# 02-MCU.net
KiCad netlist of a schematic drawn in Altium Designer
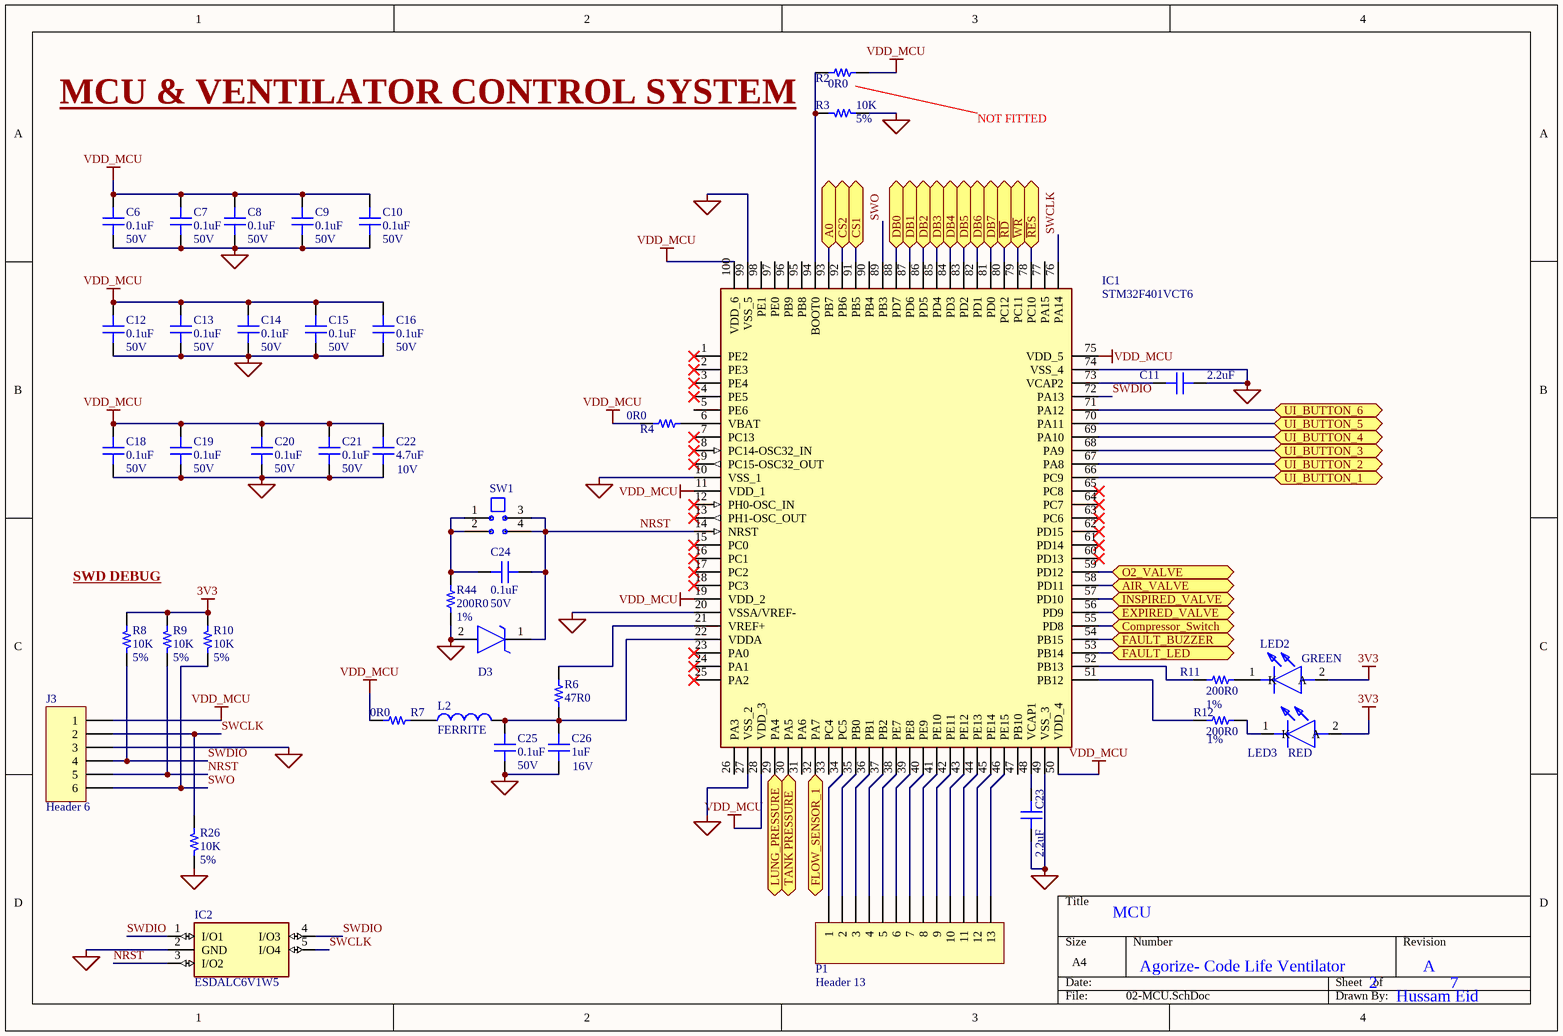
[diagram p0: 02-MCU.SchDoc]

(export (version "E")
  (design (tool "Eeschema 10.0.6"))
  (components
    (comp (ref "C6")
      (value "0.1uF")
      (footprint "CAP 0603/1608")
      (description "CAP CER 0.1UF 50V X7R 0603")
      (fields (field (name "TOLERANCE") "20%") (field (name "VOLTAGE RATING") "50V"))
      (libsource (lib "Celestial Library Database") (part "Capacitor"))
    )
    (comp (ref "C7")
      (value "0.1uF")
      (footprint "CAP 0603/1608")
      (description "CAP CER 0.1UF 50V X7R 0603")
      (fields (field (name "TOLERANCE") "20%") (field (name "VOLTAGE RATING") "50V"))
      (libsource (lib "Celestial Library Database") (part "Capacitor"))
    )
    (comp (ref "C8")
      (value "0.1uF")
      (footprint "CAP 0603/1608")
      (description "CAP CER 0.1UF 50V X7R 0603")
      (fields (field (name "TOLERANCE") "20%") (field (name "VOLTAGE RATING") "50V"))
      (libsource (lib "Celestial Library Database") (part "Capacitor"))
    )
    (comp (ref "C9")
      (value "0.1uF")
      (footprint "CAP 0603/1608")
      (description "CAP CER 0.1UF 50V X7R 0603")
      (fields (field (name "TOLERANCE") "20%") (field (name "VOLTAGE RATING") "50V"))
      (libsource (lib "Celestial Library Database") (part "Capacitor"))
    )
    (comp (ref "C10")
      (value "0.1uF")
      (footprint "CAP 0603/1608")
      (description "CAP CER 0.1UF 50V X7R 0603")
      (fields (field (name "TOLERANCE") "20%") (field (name "VOLTAGE RATING") "50V"))
      (libsource (lib "Celestial Library Database") (part "Capacitor"))
    )
    (comp (ref "C11")
      (value "2.2uF")
      (footprint "CAP 0603/1608")
      (description "CAP CER 2.2UF 16V X5R 0603")
      (fields (field (name "TOLERANCE") "10%") (field (name "VOLTAGE") "16V"))
      (libsource (lib "Celestial Library Database") (part "Capacitor"))
    )
    (comp (ref "C12")
      (value "0.1uF")
      (footprint "CAP 0603/1608")
      (description "CAP CER 0.1UF 50V X7R 0603")
      (fields (field (name "TOLERANCE") "20%") (field (name "VOLTAGE RATING") "50V"))
      (libsource (lib "Celestial Library Database") (part "Capacitor"))
    )
    (comp (ref "C13")
      (value "0.1uF")
      (footprint "CAP 0603/1608")
      (description "CAP CER 0.1UF 50V X7R 0603")
      (fields (field (name "TOLERANCE") "20%") (field (name "VOLTAGE RATING") "50V"))
      (libsource (lib "Celestial Library Database") (part "Capacitor"))
    )
    (comp (ref "C14")
      (value "0.1uF")
      (footprint "CAP 0603/1608")
      (description "CAP CER 0.1UF 50V X7R 0603")
      (fields (field (name "TOLERANCE") "20%") (field (name "VOLTAGE RATING") "50V"))
      (libsource (lib "Celestial Library Database") (part "Capacitor"))
    )
    (comp (ref "C15")
      (value "0.1uF")
      (footprint "CAP 0603/1608")
      (description "CAP CER 0.1UF 50V X7R 0603")
      (fields (field (name "TOLERANCE") "20%") (field (name "VOLTAGE RATING") "50V"))
      (libsource (lib "Celestial Library Database") (part "Capacitor"))
    )
    (comp (ref "C16")
      (value "0.1uF")
      (footprint "CAP 0603/1608")
      (description "CAP CER 0.1UF 50V X7R 0603")
      (fields (field (name "TOLERANCE") "20%") (field (name "VOLTAGE RATING") "50V"))
      (libsource (lib "Celestial Library Database") (part "Capacitor"))
    )
    (comp (ref "C18")
      (value "0.1uF")
      (footprint "CAP 0603/1608")
      (description "CAP CER 0.1UF 50V X7R 0603")
      (fields (field (name "TOLERANCE") "20%") (field (name "VOLTAGE RATING") "50V"))
      (libsource (lib "Celestial Library Database") (part "Capacitor"))
    )
    (comp (ref "C19")
      (value "0.1uF")
      (footprint "CAP 0603/1608")
      (description "CAP CER 0.1UF 50V X7R 0603")
      (fields (field (name "TOLERANCE") "20%") (field (name "VOLTAGE RATING") "50V"))
      (libsource (lib "Celestial Library Database") (part "Capacitor"))
    )
    (comp (ref "C20")
      (value "0.1uF")
      (footprint "CAP 0603/1608")
      (description "CAP CER 0.1UF 50V X7R 0603")
      (fields (field (name "TOLERANCE") "20%") (field (name "VOLTAGE RATING") "50V"))
      (libsource (lib "Celestial Library Database") (part "Capacitor"))
    )
    (comp (ref "C21")
      (value "0.1uF")
      (footprint "CAP 0603/1608")
      (description "CAP CER 0.1UF 50V X7R 0603")
      (fields (field (name "TOLERANCE") "20%") (field (name "VOLTAGE RATING") "50V"))
      (libsource (lib "Celestial Library Database") (part "Capacitor"))
    )
    (comp (ref "C22")
      (value "4.7uF")
      (footprint "CAP 0603/1608")
      (description "CAP CER 4.7UF 10V X5R 0603")
      (fields (field (name "TOLERANCE") "10%") (field (name "VOLTAGE RATING") "10V"))
      (libsource (lib "Celestial Library Database") (part "Capacitor"))
    )
    (comp (ref "C23")
      (value "2.2uF")
      (footprint "CAP 0603/1608")
      (description "CAP CER 2.2UF 16V X5R 0603")
      (fields (field (name "TOLERANCE") "10%") (field (name "VOLTAGE") "16V"))
      (libsource (lib "Celestial Library Database") (part "Capacitor"))
    )
    (comp (ref "C24")
      (value "0.1uF")
      (footprint "CAP 0603/1608")
      (description "CAP CER 0.1UF 50V X7R 0603")
      (fields (field (name "TOLERANCE") "20%") (field (name "VOLTAGE RATING") "50V"))
      (libsource (lib "Celestial Library Database") (part "Capacitor"))
    )
    (comp (ref "C25")
      (value "0.1uF")
      (footprint "CAP 0603/1608")
      (description "CAP CER 0.1UF 50V X7R 0603")
      (fields (field (name "TOLERANCE") "20%") (field (name "VOLTAGE RATING") "50V"))
      (libsource (lib "Celestial Library Database") (part "Capacitor"))
    )
    (comp (ref "C26")
      (value "1uF")
      (footprint "CAP 0603/1608")
      (description "CAP CER 1UF 16V X7R 0603")
      (fields (field (name "TOLERANCE") "20%") (field (name "VOLTAGE RATING (DC)") "16V"))
      (libsource (lib "Celestial Library Database") (part "Capacitor"))
    )
    (comp (ref "D3")
      (value "ESDALC6V1-1U2")
      (footprint "SamacSys:ESDALC6V11U2")
      (description "TVS Diode (Uni-directional)")
      (fields
        (field (name "MOUSER PART NUMBER") "511-ESDALC6V1-1U2")
        (field (name "RS PART NUMBER") "7958404P")
      )
      (libsource (lib "*") (part "ESDALC6V1-1U2"))
    )
    (comp (ref "IC1")
      (value "STM32F401VCT6")
      (footprint "SamacSys:QFP50P1600X1600X160-100N")
      (description "ARM® Cortex®-M4 STM32F4 Microcontroller IC 32-Bit 84MHz 256KB (256K x 8) FLASH 100-LQFP (14x14)")
      (fields
        (field (name "MOUSER PART NUMBER") "511-STM32F401VCT6")
        (field (name "RS PART NUMBER") "7926019P")
      )
      (libsource (lib "*") (part "STM32F401VCT6"))
    )
    (comp (ref "IC2")
      (value "ESDALC6V1W5")
      (footprint "SamacSys:SOT65P210X110-5N")
      (description "Clamp  Ipp Tvs Diode Surface Mount SOT-323-5")
      (fields (field (name "MOUSER PART NUMBER") "511-ESDALC6V1W5") (field (name "RS PART NUMBER") "1787373"))
      (libsource (lib "*") (part "ESDALC6V1W5"))
    )
    (comp (ref "J3")
      (value "Header 6")
      (footprint "HDR1X6")
      (description "Header, 6-Pin")
      (fields (field (name "PUBLISHER") "Altium Limited"))
      (libsource (lib "Miscellaneous Connectors") (part "Header 6"))
    )
    (comp (ref "L2")
      (value "FERRITE")
      (footprint "BEADC1608X95N")
      (description "FERRITE BEAD 300 OHM 0603 1LN")
      (fields (field (name "TOLERANCE") "25%"))
      (libsource (lib "Miscellaneous Devices") (part "Inductor"))
    )
    (comp (ref "LED2")
      (value "GREEN")
      (footprint "SamacSys:150060GS73220")
      (description "LED GREEN CLEAR 0603 SMD")
      (libsource (lib "*") (part "150060GS73220"))
    )
    (comp (ref "LED3")
      (value "RED")
      (footprint "SamacSys:150060GS73220")
      (description "LED GREEN CLEAR 0603 SMD")
      (libsource (lib "*") (part "150060GS73220"))
    )
    (comp (ref "P1")
      (value "Header 13")
      (footprint "HDR1X13")
      (description "Header, 13-Pin")
      (fields (field (name "PUBLISHER") "Altium Limited"))
      (libsource (lib "Miscellaneous Connectors") (part "Header 13"))
    )
    (comp (ref "R2")
      (value "0R0")
      (footprint "RES 0603/1608")
      (description "RES SMD 0 OHM JUMPER 1/10W 0603")
      (fields (field (name "TOLERANCE") "0%"))
      (libsource (lib "Celestial Library Database") (part "Resistor"))
    )
    (comp (ref "R3")
      (value "10K")
      (footprint "RES 0603/1608")
      (description "RES SMD 10K OHM 5% 1/10W 0603")
      (fields (field (name "TOLERANCE") "5%"))
      (libsource (lib "Celestial Library Database") (part "Resistor"))
    )
    (comp (ref "R4")
      (value "0R0")
      (footprint "RES 0603/1608")
      (description "RES SMD 0 OHM JUMPER 1/10W 0603")
      (fields (field (name "TOLERANCE") "0%"))
      (libsource (lib "Celestial Library Database") (part "Resistor"))
    )
    (comp (ref "R6")
      (value "47R0")
      (footprint "RES 0603/1608")
      (description "RESISTOR 47 Ohms ±5% 0.1W, 1/10W Chip Resistor 0603")
      (libsource (lib "Celestial Library Database") (part "Resistor"))
    )
    (comp (ref "R7")
      (value "0R0")
      (footprint "RES 0603/1608")
      (description "RES SMD 0 OHM JUMPER 1/10W 0603")
      (fields (field (name "TOLERANCE") "0%"))
      (libsource (lib "Celestial Library Database") (part "Resistor"))
    )
    (comp (ref "R8")
      (value "10K")
      (footprint "RES 0603/1608")
      (description "RES SMD 10K OHM 5% 1/10W 0603")
      (fields (field (name "TOLERANCE") "5%"))
      (libsource (lib "Celestial Library Database") (part "Resistor"))
    )
    (comp (ref "R9")
      (value "10K")
      (footprint "RES 0603/1608")
      (description "RES SMD 10K OHM 5% 1/10W 0603")
      (fields (field (name "TOLERANCE") "5%"))
      (libsource (lib "Celestial Library Database") (part "Resistor"))
    )
    (comp (ref "R10")
      (value "10K")
      (footprint "RES 0603/1608")
      (description "RES SMD 10K OHM 5% 1/10W 0603")
      (fields (field (name "TOLERANCE") "5%"))
      (libsource (lib "Celestial Library Database") (part "Resistor"))
    )
    (comp (ref "R11")
      (value "200R0")
      (footprint "RES 1206/3216")
      (description "RES SMD 10K OHM 1% 1/4W 1206")
      (fields (field (name "TOLERANCE") "1%"))
      (libsource (lib "Celestial Library Database") (part "Resistor"))
    )
    (comp (ref "R12")
      (value "200R0")
      (footprint "RES 1206/3216")
      (description "RES SMD 10K OHM 1% 1/4W 1206")
      (fields (field (name "TOLERANCE") "1%"))
      (libsource (lib "Celestial Library Database") (part "Resistor"))
    )
    (comp (ref "R26")
      (value "10K")
      (footprint "RES 0603/1608")
      (description "RES SMD 10K OHM 5% 1/10W 0603")
      (fields (field (name "TOLERANCE") "5%"))
      (libsource (lib "Celestial Library Database") (part "Resistor"))
    )
    (comp (ref "R44")
      (value "200R0")
      (footprint "RES 1206/3216")
      (description "RES SMD 10K OHM 1% 1/4W 1206")
      (fields (field (name "TOLERANCE") "1%"))
      (libsource (lib "Celestial Library Database") (part "Resistor"))
    )
    (comp (ref "SW1")
      (value "Tactle switch")
      (footprint "PTS526SM15SMTR2LFS")
      (description "Tactile Switch SPST-NO Top Actuated Surface Mount")
      (libsource (lib "Schlib1") (part "Tactle switch"))
    )
  )
  (nets
    (net (code "1") (name "/A0") (class "Default")
      (node (ref "IC1") (pin "93") (pinfunction "PB7_93") (pintype "passive"))
    )
    (net (code "2") (name "/AIR_VALVE") (class "Default")
      (node (ref "IC1") (pin "58") (pinfunction "PD11_58") (pintype "passive"))
    )
    (net (code "3") (name "/CS1") (class "Default")
      (node (ref "IC1") (pin "91") (pinfunction "PB5_91") (pintype "passive"))
    )
    (net (code "4") (name "/CS2") (class "Default")
      (node (ref "IC1") (pin "92") (pinfunction "PB6_92") (pintype "passive"))
    )
    (net (code "5") (name "/Compressor_Switch") (class "Default")
      (node (ref "IC1") (pin "55") (pinfunction "PD8_55") (pintype "passive"))
    )
    (net (code "6") (name "/DB0") (class "Default")
      (node (ref "IC1") (pin "88") (pinfunction "PD7_88") (pintype "passive"))
    )
    (net (code "7") (name "/DB1") (class "Default")
      (node (ref "IC1") (pin "87") (pinfunction "PD6_87") (pintype "passive"))
    )
    (net (code "8") (name "/DB2") (class "Default")
      (node (ref "IC1") (pin "86") (pinfunction "PD5_86") (pintype "passive"))
    )
    (net (code "9") (name "/DB3") (class "Default")
      (node (ref "IC1") (pin "85") (pinfunction "PD4_85") (pintype "passive"))
    )
    (net (code "10") (name "/DB4") (class "Default")
      (node (ref "IC1") (pin "84") (pinfunction "PD3_84") (pintype "passive"))
    )
    (net (code "11") (name "/DB5") (class "Default")
      (node (ref "IC1") (pin "83") (pinfunction "PD2_83") (pintype "passive"))
    )
    (net (code "12") (name "/DB6") (class "Default")
      (node (ref "IC1") (pin "82") (pinfunction "PD1_82") (pintype "passive"))
    )
    (net (code "13") (name "/DB7") (class "Default")
      (node (ref "IC1") (pin "81") (pinfunction "PD0_81") (pintype "passive"))
    )
    (net (code "14") (name "/EXPIRED_VALVE") (class "Default")
      (node (ref "IC1") (pin "56") (pinfunction "PD9_56") (pintype "passive"))
    )
    (net (code "15") (name "/FAULT_BUZZER") (class "Default")
      (node (ref "IC1") (pin "54") (pinfunction "PB15_54") (pintype "passive"))
    )
    (net (code "16") (name "/FAULT_LED") (class "Default")
      (node (ref "IC1") (pin "53") (pinfunction "PB14_53") (pintype "passive"))
    )
    (net (code "17") (name "/FLOW_SENSOR_1") (class "Default")
      (node (ref "IC1") (pin "32") (pinfunction "PA7_32") (pintype "passive"))
    )
    (net (code "18") (name "/INSPIRED_VALVE") (class "Default")
      (node (ref "IC1") (pin "57") (pinfunction "PD10_57") (pintype "passive"))
    )
    (net (code "19") (name "/LUNG_PRESSURE") (class "Default")
      (node (ref "IC1") (pin "29") (pinfunction "PA4_29") (pintype "passive"))
    )
    (net (code "20") (name "/NRST") (class "Default")
      (node (ref "C24") (pin "2") (pinfunction "2_2") (pintype "passive"))
      (node (ref "D3") (pin "1") (pinfunction "K_1") (pintype "passive"))
      (node (ref "IC1") (pin "14") (pinfunction "NRST_14") (pintype "input"))
      (node (ref "IC2") (pin "3") (pinfunction "I/O2_3") (pintype "bidirectional"))
      (node (ref "J3") (pin "5") (pinfunction "5_5") (pintype "passive"))
      (node (ref "R9") (pin "2") (pinfunction "2_2") (pintype "passive"))
      (node (ref "SW1") (pin "3") (pinfunction "3_3") (pintype "passive"))
      (node (ref "SW1") (pin "4") (pinfunction "4_4") (pintype "passive"))
    )
    (net (code "21") (name "/O2_VALVE") (class "Default")
      (node (ref "IC1") (pin "59") (pinfunction "PD12_59") (pintype "passive"))
    )
    (net (code "22") (name "/SWCLK") (class "Default")
      (node (ref "IC1") (pin "76") (pinfunction "PA14_76") (pintype "passive"))
      (node (ref "IC2") (pin "5") (pinfunction "I/O4_5") (pintype "bidirectional"))
      (node (ref "J3") (pin "2") (pinfunction "2_2") (pintype "passive"))
      (node (ref "R26") (pin "2") (pinfunction "2_2") (pintype "passive"))
    )
    (net (code "23") (name "/SWDIO") (class "Default")
      (node (ref "IC1") (pin "72") (pinfunction "PA13_72") (pintype "passive"))
      (node (ref "IC2") (pin "1") (pinfunction "I/O1_1") (pintype "bidirectional"))
      (node (ref "IC2") (pin "4") (pinfunction "I/O3_4") (pintype "bidirectional"))
      (node (ref "J3") (pin "4") (pinfunction "4_4") (pintype "passive"))
      (node (ref "R8") (pin "2") (pinfunction "2_2") (pintype "passive"))
    )
    (net (code "24") (name "/SWO") (class "Default")
      (node (ref "IC1") (pin "89") (pinfunction "PB3_89") (pintype "passive"))
      (node (ref "J3") (pin "6") (pinfunction "6_6") (pintype "passive"))
      (node (ref "R10") (pin "2") (pinfunction "2_2") (pintype "passive"))
    )
    (net (code "25") (name "/TANK PRESSURE") (class "Default")
      (node (ref "IC1") (pin "30") (pinfunction "PA5_30") (pintype "passive"))
    )
    (net (code "26") (name "/UI_BUTTON_1") (class "Default")
      (node (ref "IC1") (pin "66") (pinfunction "PC9_66") (pintype "passive"))
    )
    (net (code "27") (name "/UI_BUTTON_2") (class "Default")
      (node (ref "IC1") (pin "67") (pinfunction "PA8_67") (pintype "passive"))
    )
    (net (code "28") (name "/UI_BUTTON_3") (class "Default")
      (node (ref "IC1") (pin "68") (pinfunction "PA9_68") (pintype "passive"))
    )
    (net (code "29") (name "/UI_BUTTON_4") (class "Default")
      (node (ref "IC1") (pin "69") (pinfunction "PA10_69") (pintype "passive"))
    )
    (net (code "30") (name "/UI_BUTTON_5") (class "Default")
      (node (ref "IC1") (pin "70") (pinfunction "PA11_70") (pintype "passive"))
    )
    (net (code "31") (name "/UI_BUTTON_6") (class "Default")
      (node (ref "IC1") (pin "71") (pinfunction "PA12_71") (pintype "passive"))
    )
    (net (code "32") (name "/~{RD}") (class "Default")
      (node (ref "IC1") (pin "80") (pinfunction "PC12_80") (pintype "passive"))
    )
    (net (code "33") (name "/~{RE}S") (class "Default")
      (node (ref "IC1") (pin "78") (pinfunction "PC10_78") (pintype "passive"))
    )
    (net (code "34") (name "/~{WR}") (class "Default")
      (node (ref "IC1") (pin "79") (pinfunction "PC11_79") (pintype "passive"))
    )
    (net (code "35") (name "3V3") (class "Default")
      (node (ref "LED2") (pin "2") (pinfunction "A_2") (pintype "passive"))
      (node (ref "LED3") (pin "2") (pinfunction "A_2") (pintype "passive"))
      (node (ref "R10") (pin "1") (pinfunction "1_1") (pintype "passive"))
      (node (ref "R8") (pin "1") (pinfunction "1_1") (pintype "passive"))
      (node (ref "R9") (pin "1") (pinfunction "1_1") (pintype "passive"))
    )
    (net (code "36") (name "COM") (class "Default")
      (node (ref "C10") (pin "2") (pinfunction "2_2") (pintype "passive"))
      (node (ref "C11") (pin "2") (pinfunction "2_2") (pintype "passive"))
      (node (ref "C12") (pin "2") (pinfunction "2_2") (pintype "passive"))
      (node (ref "C13") (pin "2") (pinfunction "2_2") (pintype "passive"))
      (node (ref "C14") (pin "2") (pinfunction "2_2") (pintype "passive"))
      (node (ref "C15") (pin "2") (pinfunction "2_2") (pintype "passive"))
      (node (ref "C16") (pin "2") (pinfunction "2_2") (pintype "passive"))
      (node (ref "C18") (pin "2") (pinfunction "2_2") (pintype "passive"))
      (node (ref "C19") (pin "2") (pinfunction "2_2") (pintype "passive"))
      (node (ref "C20") (pin "2") (pinfunction "2_2") (pintype "passive"))
      (node (ref "C21") (pin "2") (pinfunction "2_2") (pintype "passive"))
      (node (ref "C22") (pin "2") (pinfunction "2_2") (pintype "passive"))
      (node (ref "C23") (pin "1") (pinfunction "1_1") (pintype "passive"))
      (node (ref "C25") (pin "2") (pinfunction "2_2") (pintype "passive"))
      (node (ref "C26") (pin "2") (pinfunction "2_2") (pintype "passive"))
      (node (ref "C6") (pin "2") (pinfunction "2_2") (pintype "passive"))
      (node (ref "C7") (pin "2") (pinfunction "2_2") (pintype "passive"))
      (node (ref "C8") (pin "2") (pinfunction "2_2") (pintype "passive"))
      (node (ref "C9") (pin "2") (pinfunction "2_2") (pintype "passive"))
      (node (ref "D3") (pin "2") (pinfunction "A_2") (pintype "passive"))
      (node (ref "IC1") (pin "10") (pinfunction "VSS_1_10") (pintype "power_in"))
      (node (ref "IC1") (pin "20") (pinfunction "VSSA/VREF-_20") (pintype "power_in"))
      (node (ref "IC1") (pin "27") (pinfunction "VSS_2_27") (pintype "power_in"))
      (node (ref "IC1") (pin "49") (pinfunction "VSS_3_49") (pintype "power_in"))
      (node (ref "IC1") (pin "74") (pinfunction "VSS_4_74") (pintype "power_in"))
      (node (ref "IC1") (pin "99") (pinfunction "VSS_5_99") (pintype "power_in"))
      (node (ref "IC2") (pin "2") (pinfunction "GND_2") (pintype "power_in"))
      (node (ref "J3") (pin "3") (pinfunction "3_3") (pintype "passive"))
      (node (ref "R26") (pin "1") (pinfunction "1_1") (pintype "passive"))
      (node (ref "R3") (pin "1") (pinfunction "1_1") (pintype "passive"))
      (node (ref "R44") (pin "1") (pinfunction "1_1") (pintype "passive"))
    )
    (net (code "37") (name "Net-(C24-Pad1)") (class "Default")
      (node (ref "C24") (pin "1") (pinfunction "1_1") (pintype "passive"))
      (node (ref "R44") (pin "2") (pinfunction "2_2") (pintype "passive"))
      (node (ref "SW1") (pin "1") (pinfunction "1_1") (pintype "passive"))
      (node (ref "SW1") (pin "2") (pinfunction "2_2") (pintype "passive"))
    )
    (net (code "38") (name "Net-(IC1-BOOT0)") (class "Default")
      (node (ref "IC1") (pin "94") (pinfunction "BOOT0_94") (pintype "passive"))
      (node (ref "R2") (pin "1") (pinfunction "1_1") (pintype "passive"))
      (node (ref "R3") (pin "2") (pinfunction "2_2") (pintype "passive"))
    )
    (net (code "39") (name "Net-(IC1-PB0)") (class "Default")
      (node (ref "IC1") (pin "35") (pinfunction "PB0_35") (pintype "passive"))
      (node (ref "P1") (pin "2") (pinfunction "2_2") (pintype "passive"))
    )
    (net (code "40") (name "Net-(IC1-PB1)") (class "Default")
      (node (ref "IC1") (pin "36") (pinfunction "PB1_36") (pintype "passive"))
      (node (ref "P1") (pin "3") (pinfunction "3_3") (pintype "passive"))
    )
    (net (code "41") (name "Net-(IC1-PB2)") (class "Default")
      (node (ref "IC1") (pin "37") (pinfunction "PB2_37") (pintype "passive"))
      (node (ref "P1") (pin "4") (pinfunction "4_4") (pintype "passive"))
    )
    (net (code "42") (name "Net-(IC1-PB12)") (class "Default")
      (node (ref "IC1") (pin "51") (pinfunction "PB12_51") (pintype "passive"))
      (node (ref "R12") (pin "1") (pinfunction "1_1") (pintype "passive"))
    )
    (net (code "43") (name "Net-(IC1-PB13)") (class "Default")
      (node (ref "IC1") (pin "52") (pinfunction "PB13_52") (pintype "passive"))
      (node (ref "R11") (pin "1") (pinfunction "1_1") (pintype "passive"))
    )
    (net (code "44") (name "Net-(IC1-PC5)") (class "Default")
      (node (ref "IC1") (pin "34") (pinfunction "PC5_34") (pintype "passive"))
      (node (ref "P1") (pin "1") (pinfunction "1_1") (pintype "passive"))
    )
    (net (code "45") (name "Net-(IC1-PE7)") (class "Default")
      (node (ref "IC1") (pin "38") (pinfunction "PE7_38") (pintype "passive"))
      (node (ref "P1") (pin "5") (pinfunction "5_5") (pintype "passive"))
    )
    (net (code "46") (name "Net-(IC1-PE8)") (class "Default")
      (node (ref "IC1") (pin "39") (pinfunction "PE8_39") (pintype "passive"))
      (node (ref "P1") (pin "6") (pinfunction "6_6") (pintype "passive"))
    )
    (net (code "47") (name "Net-(IC1-PE9)") (class "Default")
      (node (ref "IC1") (pin "40") (pinfunction "PE9_40") (pintype "passive"))
      (node (ref "P1") (pin "7") (pinfunction "7_7") (pintype "passive"))
    )
    (net (code "48") (name "Net-(IC1-PE10)") (class "Default")
      (node (ref "IC1") (pin "41") (pinfunction "PE10_41") (pintype "passive"))
      (node (ref "P1") (pin "8") (pinfunction "8_8") (pintype "passive"))
    )
    (net (code "49") (name "Net-(IC1-PE11)") (class "Default")
      (node (ref "IC1") (pin "42") (pinfunction "PE11_42") (pintype "passive"))
      (node (ref "P1") (pin "9") (pinfunction "9_9") (pintype "passive"))
    )
    (net (code "50") (name "Net-(IC1-PE12)") (class "Default")
      (node (ref "IC1") (pin "43") (pinfunction "PE12_43") (pintype "passive"))
      (node (ref "P1") (pin "10") (pinfunction "10_10") (pintype "passive"))
    )
    (net (code "51") (name "Net-(IC1-PE13)") (class "Default")
      (node (ref "IC1") (pin "44") (pinfunction "PE13_44") (pintype "passive"))
      (node (ref "P1") (pin "11") (pinfunction "11_11") (pintype "passive"))
    )
    (net (code "52") (name "Net-(IC1-PE14)") (class "Default")
      (node (ref "IC1") (pin "45") (pinfunction "PE14_45") (pintype "passive"))
      (node (ref "P1") (pin "12") (pinfunction "12_12") (pintype "passive"))
    )
    (net (code "53") (name "Net-(IC1-PE15)") (class "Default")
      (node (ref "IC1") (pin "46") (pinfunction "PE15_46") (pintype "passive"))
      (node (ref "P1") (pin "13") (pinfunction "13_13") (pintype "passive"))
    )
    (net (code "54") (name "Net-(IC1-VBAT)") (class "Default")
      (node (ref "IC1") (pin "6") (pinfunction "VBAT_6") (pintype "passive"))
      (node (ref "R4") (pin "2") (pinfunction "2_2") (pintype "passive"))
    )
    (net (code "55") (name "Net-(IC1-VCAP1)") (class "Default")
      (node (ref "C23") (pin "2") (pinfunction "2_2") (pintype "passive"))
      (node (ref "IC1") (pin "48") (pinfunction "VCAP1_48") (pintype "passive"))
    )
    (net (code "56") (name "Net-(IC1-VCAP2)") (class "Default")
      (node (ref "C11") (pin "1") (pinfunction "1_1") (pintype "passive"))
      (node (ref "IC1") (pin "73") (pinfunction "VCAP2_73") (pintype "passive"))
    )
    (net (code "57") (name "Net-(IC1-VDDA)") (class "Default")
      (node (ref "C25") (pin "1") (pinfunction "1_1") (pintype "passive"))
      (node (ref "C26") (pin "1") (pinfunction "1_1") (pintype "passive"))
      (node (ref "IC1") (pin "22") (pinfunction "VDDA_22") (pintype "power_in"))
      (node (ref "L2") (pin "2") (pinfunction "2_2") (pintype "passive"))
      (node (ref "R6") (pin "1") (pinfunction "1_1") (pintype "passive"))
    )
    (net (code "58") (name "Net-(IC1-VREF+)") (class "Default")
      (node (ref "IC1") (pin "21") (pinfunction "VREF+_21") (pintype "passive"))
      (node (ref "R6") (pin "2") (pinfunction "2_2") (pintype "passive"))
    )
    (net (code "59") (name "Net-(L2-Pad1)") (class "Default")
      (node (ref "L2") (pin "1") (pinfunction "1_1") (pintype "passive"))
      (node (ref "R7") (pin "2") (pinfunction "2_2") (pintype "passive"))
    )
    (net (code "60") (name "Net-(LED2-K)") (class "Default")
      (node (ref "LED2") (pin "1") (pinfunction "K_1") (pintype "passive"))
      (node (ref "R11") (pin "2") (pinfunction "2_2") (pintype "passive"))
    )
    (net (code "61") (name "Net-(LED3-K)") (class "Default")
      (node (ref "LED3") (pin "1") (pinfunction "K_1") (pintype "passive"))
      (node (ref "R12") (pin "2") (pinfunction "2_2") (pintype "passive"))
    )
    (net (code "62") (name "VDD_MCU") (class "Default")
      (node (ref "C10") (pin "1") (pinfunction "1_1") (pintype "passive"))
      (node (ref "C12") (pin "1") (pinfunction "1_1") (pintype "passive"))
      (node (ref "C13") (pin "1") (pinfunction "1_1") (pintype "passive"))
      (node (ref "C14") (pin "1") (pinfunction "1_1") (pintype "passive"))
      (node (ref "C15") (pin "1") (pinfunction "1_1") (pintype "passive"))
      (node (ref "C16") (pin "1") (pinfunction "1_1") (pintype "passive"))
      (node (ref "C18") (pin "1") (pinfunction "1_1") (pintype "passive"))
      (node (ref "C19") (pin "1") (pinfunction "1_1") (pintype "passive"))
      (node (ref "C20") (pin "1") (pinfunction "1_1") (pintype "passive"))
      (node (ref "C21") (pin "1") (pinfunction "1_1") (pintype "passive"))
      (node (ref "C22") (pin "1") (pinfunction "1_1") (pintype "passive"))
      (node (ref "C6") (pin "1") (pinfunction "1_1") (pintype "passive"))
      (node (ref "C7") (pin "1") (pinfunction "1_1") (pintype "passive"))
      (node (ref "C8") (pin "1") (pinfunction "1_1") (pintype "passive"))
      (node (ref "C9") (pin "1") (pinfunction "1_1") (pintype "passive"))
      (node (ref "IC1") (pin "100") (pinfunction "VDD_6_100") (pintype "power_in"))
      (node (ref "IC1") (pin "11") (pinfunction "VDD_1_11") (pintype "power_in"))
      (node (ref "IC1") (pin "19") (pinfunction "VDD_2_19") (pintype "power_in"))
      (node (ref "IC1") (pin "28") (pinfunction "VDD_3_28") (pintype "power_in"))
      (node (ref "IC1") (pin "50") (pinfunction "VDD_4_50") (pintype "power_in"))
      (node (ref "IC1") (pin "75") (pinfunction "VDD_5_75") (pintype "power_in"))
      (node (ref "J3") (pin "1") (pinfunction "1_1") (pintype "passive"))
      (node (ref "R2") (pin "2") (pinfunction "2_2") (pintype "passive"))
      (node (ref "R4") (pin "1") (pinfunction "1_1") (pintype "passive"))
      (node (ref "R7") (pin "1") (pinfunction "1_1") (pintype "passive"))
    )
    (net (code "63") (name "unconnected-(IC1-PA0-Pad23)") (class "Default")
      (node (ref "IC1") (pin "23") (pinfunction "PA0_23") (pintype "passive+no_connect"))
    )
    (net (code "64") (name "unconnected-(IC1-PA1-Pad24)") (class "Default")
      (node (ref "IC1") (pin "24") (pinfunction "PA1_24") (pintype "passive+no_connect"))
    )
    (net (code "65") (name "unconnected-(IC1-PA2-Pad25)") (class "Default")
      (node (ref "IC1") (pin "25") (pinfunction "PA2_25") (pintype "passive+no_connect"))
    )
    (net (code "66") (name "unconnected-(IC1-PA3-Pad26)") (class "Default")
      (node (ref "IC1") (pin "26") (pinfunction "PA3_26") (pintype "passive"))
    )
    (net (code "67") (name "unconnected-(IC1-PA6-Pad31)") (class "Default")
      (node (ref "IC1") (pin "31") (pinfunction "PA6_31") (pintype "passive"))
    )
    (net (code "68") (name "unconnected-(IC1-PA15-Pad77)") (class "Default")
      (node (ref "IC1") (pin "77") (pinfunction "PA15_77") (pintype "passive"))
    )
    (net (code "69") (name "unconnected-(IC1-PB4-Pad90)") (class "Default")
      (node (ref "IC1") (pin "90") (pinfunction "PB4_90") (pintype "passive"))
    )
    (net (code "70") (name "unconnected-(IC1-PB8-Pad95)") (class "Default")
      (node (ref "IC1") (pin "95") (pinfunction "PB8_95") (pintype "passive"))
    )
    (net (code "71") (name "unconnected-(IC1-PB9-Pad96)") (class "Default")
      (node (ref "IC1") (pin "96") (pinfunction "PB9_96") (pintype "passive"))
    )
    (net (code "72") (name "unconnected-(IC1-PB10-Pad47)") (class "Default")
      (node (ref "IC1") (pin "47") (pinfunction "PB10_47") (pintype "passive"))
    )
    (net (code "73") (name "unconnected-(IC1-PC0-Pad15)") (class "Default")
      (node (ref "IC1") (pin "15") (pinfunction "PC0_15") (pintype "passive+no_connect"))
    )
    (net (code "74") (name "unconnected-(IC1-PC1-Pad16)") (class "Default")
      (node (ref "IC1") (pin "16") (pinfunction "PC1_16") (pintype "passive+no_connect"))
    )
    (net (code "75") (name "unconnected-(IC1-PC2-Pad17)") (class "Default")
      (node (ref "IC1") (pin "17") (pinfunction "PC2_17") (pintype "passive+no_connect"))
    )
    (net (code "76") (name "unconnected-(IC1-PC3-Pad18)") (class "Default")
      (node (ref "IC1") (pin "18") (pinfunction "PC3_18") (pintype "passive+no_connect"))
    )
    (net (code "77") (name "unconnected-(IC1-PC4-Pad33)") (class "Default")
      (node (ref "IC1") (pin "33") (pinfunction "PC4_33") (pintype "passive"))
    )
    (net (code "78") (name "unconnected-(IC1-PC6-Pad63)") (class "Default")
      (node (ref "IC1") (pin "63") (pinfunction "PC6_63") (pintype "passive+no_connect"))
    )
    (net (code "79") (name "unconnected-(IC1-PC7-Pad64)") (class "Default")
      (node (ref "IC1") (pin "64") (pinfunction "PC7_64") (pintype "passive+no_connect"))
    )
    (net (code "80") (name "unconnected-(IC1-PC8-Pad65)") (class "Default")
      (node (ref "IC1") (pin "65") (pinfunction "PC8_65") (pintype "passive+no_connect"))
    )
    (net (code "81") (name "unconnected-(IC1-PC13-Pad7)") (class "Default")
      (node (ref "IC1") (pin "7") (pinfunction "PC13_7") (pintype "passive+no_connect"))
    )
    (net (code "82") (name "unconnected-(IC1-PC14-OSC32_IN-Pad8)") (class "Default")
      (node (ref "IC1") (pin "8") (pinfunction "PC14-OSC32_IN_8") (pintype "input+no_connect"))
    )
    (net (code "83") (name "unconnected-(IC1-PC15-OSC32_OUT-Pad9)") (class "Default")
      (node (ref "IC1") (pin "9") (pinfunction "PC15-OSC32_OUT_9") (pintype "output+no_connect"))
    )
    (net (code "84") (name "unconnected-(IC1-PD13-Pad60)") (class "Default")
      (node (ref "IC1") (pin "60") (pinfunction "PD13_60") (pintype "passive+no_connect"))
    )
    (net (code "85") (name "unconnected-(IC1-PD14-Pad61)") (class "Default")
      (node (ref "IC1") (pin "61") (pinfunction "PD14_61") (pintype "passive+no_connect"))
    )
    (net (code "86") (name "unconnected-(IC1-PD15-Pad62)") (class "Default")
      (node (ref "IC1") (pin "62") (pinfunction "PD15_62") (pintype "passive+no_connect"))
    )
    (net (code "87") (name "unconnected-(IC1-PE0-Pad97)") (class "Default")
      (node (ref "IC1") (pin "97") (pinfunction "PE0_97") (pintype "passive"))
    )
    (net (code "88") (name "unconnected-(IC1-PE1-Pad98)") (class "Default")
      (node (ref "IC1") (pin "98") (pinfunction "PE1_98") (pintype "passive"))
    )
    (net (code "89") (name "unconnected-(IC1-PE2-Pad1)") (class "Default")
      (node (ref "IC1") (pin "1") (pinfunction "PE2_1") (pintype "passive+no_connect"))
    )
    (net (code "90") (name "unconnected-(IC1-PE3-Pad2)") (class "Default")
      (node (ref "IC1") (pin "2") (pinfunction "PE3_2") (pintype "passive+no_connect"))
    )
    (net (code "91") (name "unconnected-(IC1-PE4-Pad3)") (class "Default")
      (node (ref "IC1") (pin "3") (pinfunction "PE4_3") (pintype "passive+no_connect"))
    )
    (net (code "92") (name "unconnected-(IC1-PE5-Pad4)") (class "Default")
      (node (ref "IC1") (pin "4") (pinfunction "PE5_4") (pintype "passive+no_connect"))
    )
    (net (code "93") (name "unconnected-(IC1-PE6-Pad5)") (class "Default")
      (node (ref "IC1") (pin "5") (pinfunction "PE6_5") (pintype "passive"))
    )
    (net (code "94") (name "unconnected-(IC1-PH0-OSC_IN-Pad12)") (class "Default")
      (node (ref "IC1") (pin "12") (pinfunction "PH0-OSC_IN_12") (pintype "input+no_connect"))
    )
    (net (code "95") (name "unconnected-(IC1-PH1-OSC_OUT-Pad13)") (class "Default")
      (node (ref "IC1") (pin "13") (pinfunction "PH1-OSC_OUT_13") (pintype "output+no_connect"))
    )
  )
)
